# mic-preamp-stereo8x.net
KiCad netlist of a schematic drawn in EAGLE
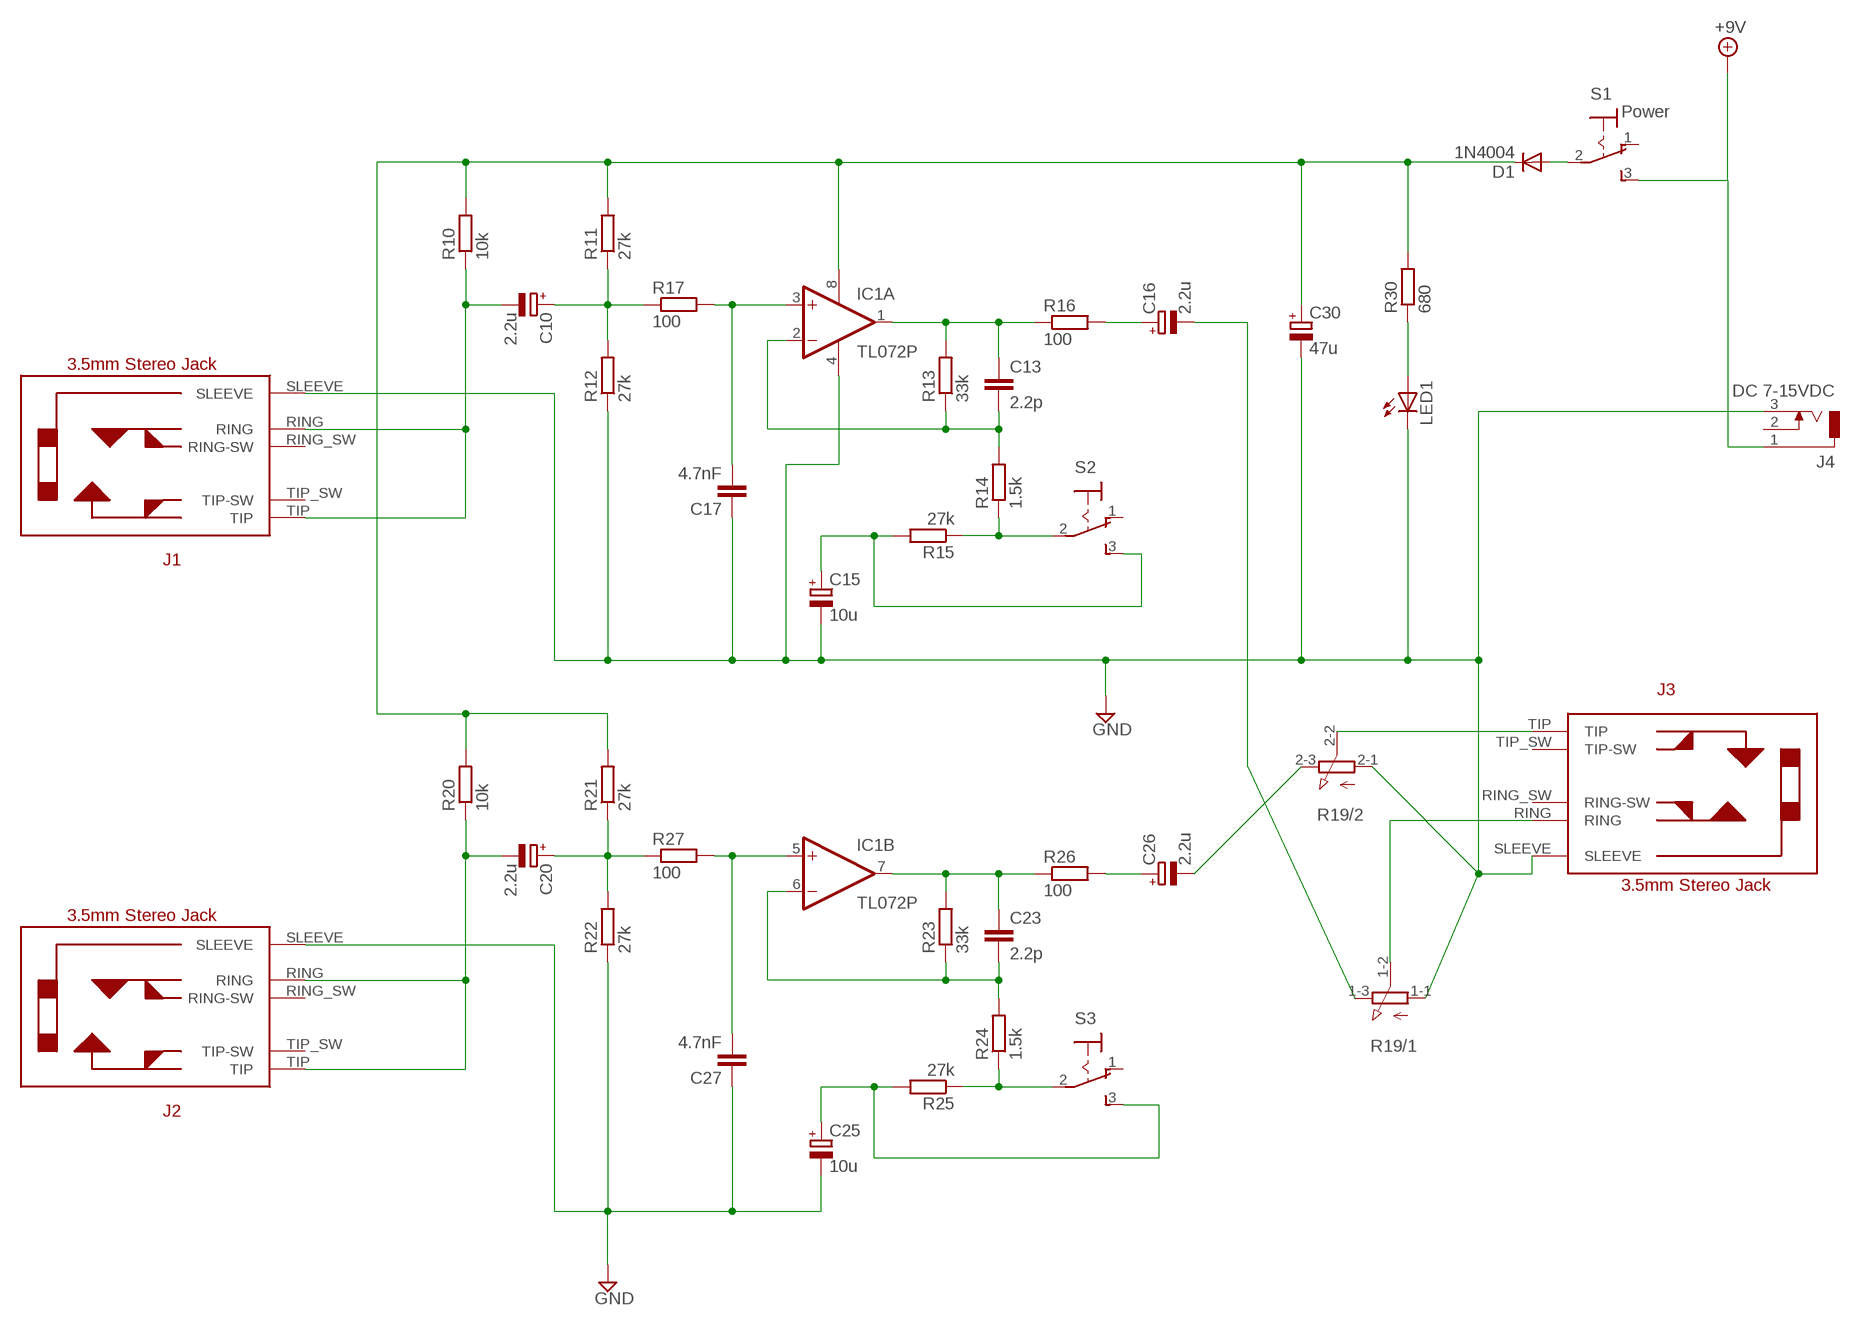
[diagram p0: schematic, sheet 1]

(export (version "E")
  (design (tool "Eeschema 10.0.6"))
  (components
    (comp (ref "C10")
      (value "2.2u")
      (footprint "eagle-import:E2-5")
      (libsource (lib "eagle-import") (part "CPOL-EUE2-5"))
    )
    (comp (ref "C13")
      (value "2.2p")
      (footprint "eagle-import:C025-024X044")
      (libsource (lib "eagle-import") (part "C-EU025-024X044"))
    )
    (comp (ref "C15")
      (value "10u")
      (footprint "eagle-import:E2-5")
      (libsource (lib "eagle-import") (part "CPOL-EUE2-5"))
    )
    (comp (ref "C16")
      (value "2.2u")
      (footprint "eagle-import:E2-5")
      (libsource (lib "eagle-import") (part "CPOL-EUE2-5"))
    )
    (comp (ref "C17")
      (value "4.7nF")
      (footprint "eagle-import:C025-024X044")
      (libsource (lib "eagle-import") (part "C-EU025-024X044"))
    )
    (comp (ref "C20")
      (value "2.2u")
      (footprint "eagle-import:E2-5")
      (libsource (lib "eagle-import") (part "CPOL-EUE2-5"))
    )
    (comp (ref "C23")
      (value "2.2p")
      (footprint "eagle-import:C025-024X044")
      (libsource (lib "eagle-import") (part "C-EU025-024X044"))
    )
    (comp (ref "C25")
      (value "10u")
      (footprint "eagle-import:E2-5")
      (libsource (lib "eagle-import") (part "CPOL-EUE2-5"))
    )
    (comp (ref "C26")
      (value "2.2u")
      (footprint "eagle-import:E2-5")
      (libsource (lib "eagle-import") (part "CPOL-EUE2-5"))
    )
    (comp (ref "C27")
      (value "4.7nF")
      (footprint "eagle-import:C025-024X044")
      (libsource (lib "eagle-import") (part "C-EU025-024X044"))
    )
    (comp (ref "C30")
      (value "47u")
      (footprint "eagle-import:E2-5")
      (libsource (lib "eagle-import") (part "CPOL-EUE2-5"))
    )
    (comp (ref "D1")
      (value "1N4004")
      (footprint "eagle-import:DO41-10")
      (libsource (lib "eagle-import") (part "1N4004"))
    )
    (comp (ref "IC1")
      (value "TL072P")
      (footprint "eagle-import:DIL08")
      (libsource (lib "eagle-import") (part "TL072P"))
    )
    (comp (ref "J1")
      (value "PICAXE_STEREOJACKSOCKET")
      (footprint "eagle-import:PICAXE_STEREOJACKSOCKET")
      (libsource (lib "eagle-import") (part "PICAXE_STEREOJACKSOCKET"))
    )
    (comp (ref "J2")
      (value "PICAXE_STEREOJACKSOCKET")
      (footprint "eagle-import:PICAXE_STEREOJACKSOCKET")
      (libsource (lib "eagle-import") (part "PICAXE_STEREOJACKSOCKET"))
    )
    (comp (ref "J3")
      (value "Stereo Out")
      (footprint "eagle-import:PICAXE_STEREOJACKSOCKET")
      (libsource (lib "eagle-import") (part "PICAXE_STEREOJACKSOCKET"))
    )
    (comp (ref "J4")
      (value "DC 7-15VDC")
      (footprint "eagle-import:DCJ0202")
      (libsource (lib "eagle-import") (part "DCJ0202"))
    )
    (comp (ref "LED1")
      (value "LED5MM")
      (footprint "eagle-import:LED5MM")
      (libsource (lib "eagle-import") (part "LED5MM"))
    )
    (comp (ref "R10")
      (value "10k")
      (footprint "eagle-import:0207_5V")
      (libsource (lib "eagle-import") (part "R-EU_0207/5V"))
    )
    (comp (ref "R11")
      (value "27k")
      (footprint "eagle-import:0207_5V")
      (libsource (lib "eagle-import") (part "R-EU_0207/5V"))
    )
    (comp (ref "R12")
      (value "27k")
      (footprint "eagle-import:0207_5V")
      (libsource (lib "eagle-import") (part "R-EU_0207/5V"))
    )
    (comp (ref "R13")
      (value "33k")
      (footprint "eagle-import:0207_5V")
      (libsource (lib "eagle-import") (part "R-EU_0207/5V"))
    )
    (comp (ref "R14")
      (value "1.5k")
      (footprint "eagle-import:0207_5V")
      (libsource (lib "eagle-import") (part "R-EU_0207/5V"))
    )
    (comp (ref "R15")
      (value "27k")
      (footprint "eagle-import:0207_5V")
      (libsource (lib "eagle-import") (part "R-EU_0207/5V"))
    )
    (comp (ref "R16")
      (value "100")
      (footprint "eagle-import:0207_5V")
      (libsource (lib "eagle-import") (part "R-EU_0207/5V"))
    )
    (comp (ref "R17")
      (value "100")
      (footprint "eagle-import:0207_5V")
      (libsource (lib "eagle-import") (part "resistor_R-EU_0207/5V"))
    )
    (comp (ref "R19")
      (value "3RP/1610G")
      (footprint "eagle-import:3RP_1610G")
      (libsource (lib "eagle-import") (part "3RP/1610G"))
    )
    (comp (ref "R20")
      (value "10k")
      (footprint "eagle-import:0207_5V")
      (libsource (lib "eagle-import") (part "R-EU_0207/5V"))
    )
    (comp (ref "R21")
      (value "27k")
      (footprint "eagle-import:0207_5V")
      (libsource (lib "eagle-import") (part "R-EU_0207/5V"))
    )
    (comp (ref "R22")
      (value "27k")
      (footprint "eagle-import:0207_5V")
      (libsource (lib "eagle-import") (part "R-EU_0207/5V"))
    )
    (comp (ref "R23")
      (value "33k")
      (footprint "eagle-import:0207_5V")
      (libsource (lib "eagle-import") (part "R-EU_0207/5V"))
    )
    (comp (ref "R24")
      (value "1.5k")
      (footprint "eagle-import:0207_5V")
      (libsource (lib "eagle-import") (part "R-EU_0207/5V"))
    )
    (comp (ref "R25")
      (value "27k")
      (footprint "eagle-import:0207_5V")
      (libsource (lib "eagle-import") (part "R-EU_0207/5V"))
    )
    (comp (ref "R26")
      (value "100")
      (footprint "eagle-import:0207_5V")
      (libsource (lib "eagle-import") (part "R-EU_0207/5V"))
    )
    (comp (ref "R27")
      (value "100")
      (footprint "eagle-import:0207_5V")
      (libsource (lib "eagle-import") (part "resistor_R-EU_0207/5V"))
    )
    (comp (ref "R30")
      (value "680")
      (footprint "eagle-import:0207_5V")
      (libsource (lib "eagle-import") (part "R-EU_0207/5V"))
    )
    (comp (ref "S1")
      (value "Power")
      (footprint "eagle-import:M9040P")
      (libsource (lib "eagle-import") (part "M9040P"))
    )
    (comp (ref "S2")
      (value "M9040P")
      (footprint "eagle-import:M9040P")
      (libsource (lib "eagle-import") (part "M9040P"))
    )
    (comp (ref "S3")
      (value "M9040P")
      (footprint "eagle-import:M9040P")
      (libsource (lib "eagle-import") (part "M9040P"))
    )
  )
  (nets
    (net (code "1") (name "+9V") (class "Default")
      (node (ref "J4") (pin "1") (pinfunction "1_1") (pintype "passive"))
      (node (ref "S1") (pin "3") (pinfunction "S_3") (pintype "passive"))
    )
    (net (code "2") (name "GND") (class "Default")
      (node (ref "C15") (pin "-") (pinfunction "-_-") (pintype "passive"))
      (node (ref "C17") (pin "1") (pinfunction "1_1") (pintype "passive"))
      (node (ref "C25") (pin "-") (pinfunction "-_-") (pintype "passive"))
      (node (ref "C27") (pin "1") (pinfunction "1_1") (pintype "passive"))
      (node (ref "C30") (pin "-") (pinfunction "-_-") (pintype "passive"))
      (node (ref "IC1") (pin "4") (pinfunction "V-_4") (pintype "power_in"))
      (node (ref "J1") (pin "SLEEVE") (pinfunction "SLEEVE_SLEEVE") (pintype "bidirectional"))
      (node (ref "J2") (pin "SLEEVE") (pinfunction "SLEEVE_SLEEVE") (pintype "bidirectional"))
      (node (ref "J3") (pin "SLEEVE") (pinfunction "SLEEVE_SLEEVE") (pintype "bidirectional"))
      (node (ref "J4") (pin "3") (pinfunction "3_3") (pintype "passive"))
      (node (ref "LED1") (pin "K") (pinfunction "C_K") (pintype "passive"))
      (node (ref "R12") (pin "1") (pinfunction "1_1") (pintype "passive"))
      (node (ref "R19") (pin "1-1") (pinfunction "A_1-1") (pintype "passive"))
      (node (ref "R19") (pin "2-1") (pinfunction "A_2-1") (pintype "passive"))
      (node (ref "R22") (pin "1") (pinfunction "1_1") (pintype "passive"))
    )
    (net (code "3") (name "Net-(C10-Pad+)") (class "Default")
      (node (ref "C10") (pin "+") (pinfunction "+_+") (pintype "passive"))
      (node (ref "R11") (pin "1") (pinfunction "1_1") (pintype "passive"))
      (node (ref "R12") (pin "2") (pinfunction "2_2") (pintype "passive"))
      (node (ref "R17") (pin "1") (pinfunction "1_1") (pintype "passive"))
    )
    (net (code "4") (name "Net-(C10-Pad-)") (class "Default")
      (node (ref "C10") (pin "-") (pinfunction "-_-") (pintype "passive"))
      (node (ref "J1") (pin "RING") (pinfunction "RING_RING") (pintype "bidirectional"))
      (node (ref "J1") (pin "TIP") (pinfunction "TIP_TIP") (pintype "bidirectional"))
      (node (ref "R10") (pin "1") (pinfunction "1_1") (pintype "passive"))
    )
    (net (code "5") (name "Net-(C16-Pad+)") (class "Default")
      (node (ref "C16") (pin "+") (pinfunction "+_+") (pintype "passive"))
      (node (ref "R16") (pin "2") (pinfunction "2_2") (pintype "passive"))
    )
    (net (code "6") (name "Net-(C20-Pad+)") (class "Default")
      (node (ref "C20") (pin "+") (pinfunction "+_+") (pintype "passive"))
      (node (ref "R21") (pin "1") (pinfunction "1_1") (pintype "passive"))
      (node (ref "R22") (pin "2") (pinfunction "2_2") (pintype "passive"))
      (node (ref "R27") (pin "1") (pinfunction "1_1") (pintype "passive"))
    )
    (net (code "7") (name "Net-(C20-Pad-)") (class "Default")
      (node (ref "C20") (pin "-") (pinfunction "-_-") (pintype "passive"))
      (node (ref "J2") (pin "RING") (pinfunction "RING_RING") (pintype "bidirectional"))
      (node (ref "J2") (pin "TIP") (pinfunction "TIP_TIP") (pintype "bidirectional"))
      (node (ref "R20") (pin "1") (pinfunction "1_1") (pintype "passive"))
    )
    (net (code "8") (name "Net-(C26-Pad+)") (class "Default")
      (node (ref "C26") (pin "+") (pinfunction "+_+") (pintype "passive"))
      (node (ref "R26") (pin "2") (pinfunction "2_2") (pintype "passive"))
    )
    (net (code "9") (name "Net-(IC1A-+IN)") (class "Default")
      (node (ref "C17") (pin "2") (pinfunction "2_2") (pintype "passive"))
      (node (ref "IC1") (pin "3") (pinfunction "+IN_3") (pintype "input"))
      (node (ref "R17") (pin "2") (pinfunction "2_2") (pintype "passive"))
    )
    (net (code "10") (name "Net-(IC1A--IN)") (class "Default")
      (node (ref "C13") (pin "2") (pinfunction "2_2") (pintype "passive"))
      (node (ref "IC1") (pin "2") (pinfunction "-IN_2") (pintype "input"))
      (node (ref "R13") (pin "1") (pinfunction "1_1") (pintype "passive"))
      (node (ref "R14") (pin "2") (pinfunction "2_2") (pintype "passive"))
    )
    (net (code "11") (name "Net-(IC1A-OUT)") (class "Default")
      (node (ref "C13") (pin "1") (pinfunction "1_1") (pintype "passive"))
      (node (ref "IC1") (pin "1") (pinfunction "OUT_1") (pintype "output"))
      (node (ref "R13") (pin "2") (pinfunction "2_2") (pintype "passive"))
      (node (ref "R16") (pin "1") (pinfunction "1_1") (pintype "passive"))
    )
    (net (code "12") (name "Net-(IC1B-+IN)") (class "Default")
      (node (ref "C27") (pin "2") (pinfunction "2_2") (pintype "passive"))
      (node (ref "IC1") (pin "5") (pinfunction "+IN_5") (pintype "input"))
      (node (ref "R27") (pin "2") (pinfunction "2_2") (pintype "passive"))
    )
    (net (code "13") (name "Net-(IC1B--IN)") (class "Default")
      (node (ref "C23") (pin "2") (pinfunction "2_2") (pintype "passive"))
      (node (ref "IC1") (pin "6") (pinfunction "-IN_6") (pintype "input"))
      (node (ref "R23") (pin "1") (pinfunction "1_1") (pintype "passive"))
      (node (ref "R24") (pin "2") (pinfunction "2_2") (pintype "passive"))
    )
    (net (code "14") (name "Net-(IC1B-OUT)") (class "Default")
      (node (ref "C23") (pin "1") (pinfunction "1_1") (pintype "passive"))
      (node (ref "IC1") (pin "7") (pinfunction "OUT_7") (pintype "output"))
      (node (ref "R23") (pin "2") (pinfunction "2_2") (pintype "passive"))
      (node (ref "R26") (pin "1") (pinfunction "1_1") (pintype "passive"))
    )
    (net (code "15") (name "Net-(IC1C-V+)") (class "Default")
      (node (ref "C30") (pin "+") (pinfunction "+_+") (pintype "passive"))
      (node (ref "D1") (pin "C") (pinfunction "C_C") (pintype "passive"))
      (node (ref "IC1") (pin "8") (pinfunction "V+_8") (pintype "power_in"))
      (node (ref "R10") (pin "2") (pinfunction "2_2") (pintype "passive"))
      (node (ref "R11") (pin "2") (pinfunction "2_2") (pintype "passive"))
      (node (ref "R20") (pin "2") (pinfunction "2_2") (pintype "passive"))
      (node (ref "R21") (pin "2") (pinfunction "2_2") (pintype "passive"))
      (node (ref "R30") (pin "2") (pinfunction "2_2") (pintype "passive"))
    )
    (net (code "16") (name "Net-(LED1-PadA)") (class "Default")
      (node (ref "LED1") (pin "A") (pinfunction "A_A") (pintype "passive"))
      (node (ref "R30") (pin "1") (pinfunction "1_1") (pintype "passive"))
    )
    (net (code "17") (name "Net-(R19A-E)") (class "Default")
      (node (ref "C16") (pin "-") (pinfunction "-_-") (pintype "passive"))
      (node (ref "R19") (pin "1-3") (pinfunction "E_1-3") (pintype "passive"))
    )
    (net (code "18") (name "Net-(R19A-S)") (class "Default")
      (node (ref "J3") (pin "RING") (pinfunction "RING_RING") (pintype "bidirectional"))
      (node (ref "R19") (pin "1-2") (pinfunction "S_1-2") (pintype "passive"))
    )
    (net (code "19") (name "Net-(R19B-E)") (class "Default")
      (node (ref "C26") (pin "-") (pinfunction "-_-") (pintype "passive"))
      (node (ref "R19") (pin "2-3") (pinfunction "E_2-3") (pintype "passive"))
    )
    (net (code "20") (name "Net-(R19B-S)") (class "Default")
      (node (ref "J3") (pin "TIP") (pinfunction "TIP_TIP") (pintype "bidirectional"))
      (node (ref "R19") (pin "2-2") (pinfunction "S_2-2") (pintype "passive"))
    )
    (net (code "21") (name "Net-(S1-P)") (class "Default")
      (node (ref "D1") (pin "A") (pinfunction "A_A") (pintype "passive"))
      (node (ref "S1") (pin "2") (pinfunction "P_2") (pintype "passive"))
    )
    (net (code "22") (name "Net-(S2-P)") (class "Default")
      (node (ref "R14") (pin "1") (pinfunction "1_1") (pintype "passive"))
      (node (ref "R15") (pin "1") (pinfunction "1_1") (pintype "passive"))
      (node (ref "S2") (pin "2") (pinfunction "P_2") (pintype "passive"))
    )
    (net (code "23") (name "Net-(S2-S)") (class "Default")
      (node (ref "C15") (pin "+") (pinfunction "+_+") (pintype "passive"))
      (node (ref "R15") (pin "2") (pinfunction "2_2") (pintype "passive"))
      (node (ref "S2") (pin "3") (pinfunction "S_3") (pintype "passive"))
    )
    (net (code "24") (name "Net-(S3-P)") (class "Default")
      (node (ref "R24") (pin "1") (pinfunction "1_1") (pintype "passive"))
      (node (ref "R25") (pin "1") (pinfunction "1_1") (pintype "passive"))
      (node (ref "S3") (pin "2") (pinfunction "P_2") (pintype "passive"))
    )
    (net (code "25") (name "Net-(S3-S)") (class "Default")
      (node (ref "C25") (pin "+") (pinfunction "+_+") (pintype "passive"))
      (node (ref "R25") (pin "2") (pinfunction "2_2") (pintype "passive"))
      (node (ref "S3") (pin "3") (pinfunction "S_3") (pintype "passive"))
    )
    (net (code "26") (name "unconnected-(J1-RING-SW-PadRING_SW)") (class "Default")
      (node (ref "J1") (pin "RING_SW") (pinfunction "RING-SW_RING_SW") (pintype "bidirectional"))
    )
    (net (code "27") (name "unconnected-(J1-TIP-SW-PadTIP_SW)") (class "Default")
      (node (ref "J1") (pin "TIP_SW") (pinfunction "TIP-SW_TIP_SW") (pintype "bidirectional"))
    )
    (net (code "28") (name "unconnected-(J2-RING-SW-PadRING_SW)") (class "Default")
      (node (ref "J2") (pin "RING_SW") (pinfunction "RING-SW_RING_SW") (pintype "bidirectional"))
    )
    (net (code "29") (name "unconnected-(J2-TIP-SW-PadTIP_SW)") (class "Default")
      (node (ref "J2") (pin "TIP_SW") (pinfunction "TIP-SW_TIP_SW") (pintype "bidirectional"))
    )
    (net (code "30") (name "unconnected-(J3-RING-SW-PadRING_SW)") (class "Default")
      (node (ref "J3") (pin "RING_SW") (pinfunction "RING-SW_RING_SW") (pintype "bidirectional"))
    )
    (net (code "31") (name "unconnected-(J3-TIP-SW-PadTIP_SW)") (class "Default")
      (node (ref "J3") (pin "TIP_SW") (pinfunction "TIP-SW_TIP_SW") (pintype "bidirectional"))
    )
    (net (code "32") (name "unconnected-(J4-Pad2)") (class "Default")
      (node (ref "J4") (pin "2") (pinfunction "2_2") (pintype "passive"))
    )
    (net (code "33") (name "unconnected-(S1-O-Pad1)") (class "Default")
      (node (ref "S1") (pin "1") (pinfunction "O_1") (pintype "passive"))
    )
    (net (code "34") (name "unconnected-(S2-O-Pad1)") (class "Default")
      (node (ref "S2") (pin "1") (pinfunction "O_1") (pintype "passive"))
    )
    (net (code "35") (name "unconnected-(S3-O-Pad1)") (class "Default")
      (node (ref "S3") (pin "1") (pinfunction "O_1") (pintype "passive"))
    )
  )
)
